# RP_ComputeModule3_rev_3_0.net
KiCad netlist of a schematic drawn in Altium Designer
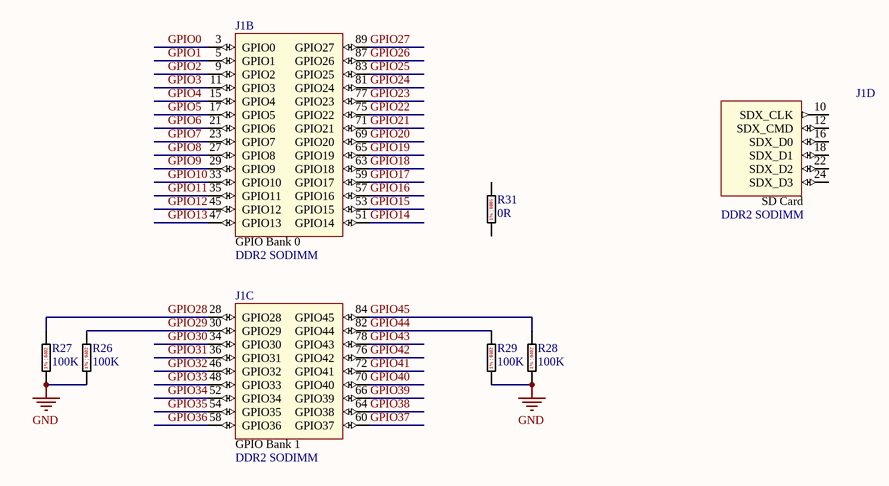
[diagram p0: RP_ComputeModule3_rev.3.0.SchDoc]

(export (version "E")
  (design (tool "Eeschema 10.0.6"))
  (components
    (comp (ref "J1")
      (value "DDR2 SODIMM")
      (footprint "TE 1473005-4 (DDR2 SO-DIMM)")
      (description "TE CONNECTIVITY / AMP         1473005-4             SOCKET IC, DIMM, DDR2, 1.8V, 200WAY")
      (fields
        (field (name "MANUFACTURER") "TE Connectivity")
        (field (name "MANUFACTURER PART NUMBER") "1473005-4")
      )
      (libsource (lib "TEConnectivity_AMP") (part "1473005-4"))
    )
    (comp (ref "R26")
      (value "100K")
      (footprint "RES0402")
      (description "Thick Film Resistors - SMD 0.125W 100Kohm 1% 200ppm")
      (fields
        (field (name "MANUFACTURER") "KOA Speer")
        (field (name "MANUFACTURER PART NUMBER") "SG73P1ETTP1003F")
      )
      (libsource (lib "KOA_Resistors") (part "SG73P1ETTP1003F"))
    )
    (comp (ref "R27")
      (value "100K")
      (footprint "RES0402")
      (description "Thick Film Resistors - SMD 0.125W 100Kohm 1% 200ppm")
      (fields
        (field (name "MANUFACTURER") "KOA Speer")
        (field (name "MANUFACTURER PART NUMBER") "SG73P1ETTP1003F")
      )
      (libsource (lib "KOA_Resistors") (part "SG73P1ETTP1003F"))
    )
    (comp (ref "R28")
      (value "100K")
      (footprint "RES0402")
      (description "Thick Film Resistors - SMD 0.125W 100Kohm 1% 200ppm")
      (fields
        (field (name "MANUFACTURER") "KOA Speer")
        (field (name "MANUFACTURER PART NUMBER") "SG73P1ETTP1003F")
      )
      (libsource (lib "KOA_Resistors") (part "SG73P1ETTP1003F"))
    )
    (comp (ref "R29")
      (value "100K")
      (footprint "RES0402")
      (description "Thick Film Resistors - SMD 0.125W 100Kohm 1% 200ppm")
      (fields
        (field (name "MANUFACTURER") "KOA Speer")
        (field (name "MANUFACTURER PART NUMBER") "SG73P1ETTP1003F")
      )
      (libsource (lib "KOA_Resistors") (part "SG73P1ETTP1003F"))
    )
    (comp (ref "R31")
      (value "0R")
      (footprint "YAGEO RES0402")
      (description "Thick Film Resistors - SMD 1/8W 0.0ohm 1%")
      (fields
        (field (name "MANUFACTURER") "Yageo")
        (field (name "MANUFACTURER PART NUMBER") "AC0805FR-070RL")
      )
      (libsource (lib "YAGEO_Library") (part "AC0805FR-070RL"))
    )
  )
  (nets
    (net (code "1") (name "/GPIO0") (class "Default")
      (node (ref "J1") (pin "3") (pinfunction "GPIO0_3") (pintype "bidirectional"))
    )
    (net (code "2") (name "/GPIO1") (class "Default")
      (node (ref "J1") (pin "5") (pinfunction "GPIO1_5") (pintype "bidirectional"))
    )
    (net (code "3") (name "/GPIO2") (class "Default")
      (node (ref "J1") (pin "9") (pinfunction "GPIO2_9") (pintype "bidirectional"))
    )
    (net (code "4") (name "/GPIO3") (class "Default")
      (node (ref "J1") (pin "11") (pinfunction "GPIO3_11") (pintype "bidirectional"))
    )
    (net (code "5") (name "/GPIO4") (class "Default")
      (node (ref "J1") (pin "15") (pinfunction "GPIO4_15") (pintype "bidirectional"))
    )
    (net (code "6") (name "/GPIO5") (class "Default")
      (node (ref "J1") (pin "17") (pinfunction "GPIO5_17") (pintype "bidirectional"))
    )
    (net (code "7") (name "/GPIO6") (class "Default")
      (node (ref "J1") (pin "21") (pinfunction "GPIO6_21") (pintype "bidirectional"))
    )
    (net (code "8") (name "/GPIO7") (class "Default")
      (node (ref "J1") (pin "23") (pinfunction "GPIO7_23") (pintype "bidirectional"))
    )
    (net (code "9") (name "/GPIO8") (class "Default")
      (node (ref "J1") (pin "27") (pinfunction "GPIO8_27") (pintype "bidirectional"))
    )
    (net (code "10") (name "/GPIO9") (class "Default")
      (node (ref "J1") (pin "29") (pinfunction "GPIO9_29") (pintype "bidirectional"))
    )
    (net (code "11") (name "/GPIO10") (class "Default")
      (node (ref "J1") (pin "33") (pinfunction "GPIO10_33") (pintype "bidirectional"))
    )
    (net (code "12") (name "/GPIO11") (class "Default")
      (node (ref "J1") (pin "35") (pinfunction "GPIO11_35") (pintype "bidirectional"))
    )
    (net (code "13") (name "/GPIO12") (class "Default")
      (node (ref "J1") (pin "45") (pinfunction "GPIO12_45") (pintype "bidirectional"))
    )
    (net (code "14") (name "/GPIO13") (class "Default")
      (node (ref "J1") (pin "47") (pinfunction "GPIO13_47") (pintype "bidirectional"))
    )
    (net (code "15") (name "/GPIO14") (class "Default")
      (node (ref "J1") (pin "51") (pinfunction "GPIO14_51") (pintype "bidirectional"))
    )
    (net (code "16") (name "/GPIO15") (class "Default")
      (node (ref "J1") (pin "53") (pinfunction "GPIO15_53") (pintype "bidirectional"))
    )
    (net (code "17") (name "/GPIO16") (class "Default")
      (node (ref "J1") (pin "57") (pinfunction "GPIO16_57") (pintype "bidirectional"))
    )
    (net (code "18") (name "/GPIO17") (class "Default")
      (node (ref "J1") (pin "59") (pinfunction "GPIO17_59") (pintype "bidirectional"))
    )
    (net (code "19") (name "/GPIO18") (class "Default")
      (node (ref "J1") (pin "63") (pinfunction "GPIO18_63") (pintype "bidirectional"))
    )
    (net (code "20") (name "/GPIO19") (class "Default")
      (node (ref "J1") (pin "65") (pinfunction "GPIO19_65") (pintype "bidirectional"))
    )
    (net (code "21") (name "/GPIO20") (class "Default")
      (node (ref "J1") (pin "69") (pinfunction "GPIO20_69") (pintype "bidirectional"))
    )
    (net (code "22") (name "/GPIO21") (class "Default")
      (node (ref "J1") (pin "71") (pinfunction "GPIO21_71") (pintype "bidirectional"))
    )
    (net (code "23") (name "/GPIO22") (class "Default")
      (node (ref "J1") (pin "75") (pinfunction "GPIO22_75") (pintype "bidirectional"))
    )
    (net (code "24") (name "/GPIO23") (class "Default")
      (node (ref "J1") (pin "77") (pinfunction "GPIO23_77") (pintype "bidirectional"))
    )
    (net (code "25") (name "/GPIO24") (class "Default")
      (node (ref "J1") (pin "81") (pinfunction "GPIO24_81") (pintype "bidirectional"))
    )
    (net (code "26") (name "/GPIO25") (class "Default")
      (node (ref "J1") (pin "83") (pinfunction "GPIO25_83") (pintype "bidirectional"))
    )
    (net (code "27") (name "/GPIO26") (class "Default")
      (node (ref "J1") (pin "87") (pinfunction "GPIO26_87") (pintype "bidirectional"))
    )
    (net (code "28") (name "/GPIO27") (class "Default")
      (node (ref "J1") (pin "89") (pinfunction "GPIO27_89") (pintype "bidirectional"))
    )
    (net (code "29") (name "/GPIO28") (class "Default")
      (node (ref "J1") (pin "28") (pinfunction "GPIO28_28") (pintype "bidirectional"))
      (node (ref "R27") (pin "1") (pinfunction "1_1") (pintype "passive"))
    )
    (net (code "30") (name "/GPIO29") (class "Default")
      (node (ref "J1") (pin "30") (pinfunction "GPIO29_30") (pintype "bidirectional"))
      (node (ref "R26") (pin "1") (pinfunction "1_1") (pintype "passive"))
    )
    (net (code "31") (name "/GPIO30") (class "Default")
      (node (ref "J1") (pin "34") (pinfunction "GPIO30_34") (pintype "bidirectional"))
    )
    (net (code "32") (name "/GPIO31") (class "Default")
      (node (ref "J1") (pin "36") (pinfunction "GPIO31_36") (pintype "bidirectional"))
    )
    (net (code "33") (name "/GPIO32") (class "Default")
      (node (ref "J1") (pin "46") (pinfunction "GPIO32_46") (pintype "bidirectional"))
    )
    (net (code "34") (name "/GPIO33") (class "Default")
      (node (ref "J1") (pin "48") (pinfunction "GPIO33_48") (pintype "bidirectional"))
    )
    (net (code "35") (name "/GPIO34") (class "Default")
      (node (ref "J1") (pin "52") (pinfunction "GPIO34_52") (pintype "bidirectional"))
    )
    (net (code "36") (name "/GPIO35") (class "Default")
      (node (ref "J1") (pin "54") (pinfunction "GPIO35_54") (pintype "bidirectional"))
    )
    (net (code "37") (name "/GPIO36") (class "Default")
      (node (ref "J1") (pin "58") (pinfunction "GPIO36_58") (pintype "bidirectional"))
    )
    (net (code "38") (name "/GPIO37") (class "Default")
      (node (ref "J1") (pin "60") (pinfunction "GPIO37_60") (pintype "bidirectional"))
    )
    (net (code "39") (name "/GPIO38") (class "Default")
      (node (ref "J1") (pin "64") (pinfunction "GPIO38_64") (pintype "bidirectional"))
    )
    (net (code "40") (name "/GPIO39") (class "Default")
      (node (ref "J1") (pin "66") (pinfunction "GPIO39_66") (pintype "bidirectional"))
    )
    (net (code "41") (name "/GPIO40") (class "Default")
      (node (ref "J1") (pin "70") (pinfunction "GPIO40_70") (pintype "bidirectional"))
    )
    (net (code "42") (name "/GPIO41") (class "Default")
      (node (ref "J1") (pin "72") (pinfunction "GPIO41_72") (pintype "bidirectional"))
    )
    (net (code "43") (name "/GPIO42") (class "Default")
      (node (ref "J1") (pin "76") (pinfunction "GPIO42_76") (pintype "bidirectional"))
    )
    (net (code "44") (name "/GPIO43") (class "Default")
      (node (ref "J1") (pin "78") (pinfunction "GPIO43_78") (pintype "bidirectional"))
    )
    (net (code "45") (name "/GPIO44") (class "Default")
      (node (ref "J1") (pin "82") (pinfunction "GPIO44_82") (pintype "bidirectional"))
      (node (ref "R29") (pin "1") (pinfunction "1_1") (pintype "passive"))
    )
    (net (code "46") (name "/GPIO45") (class "Default")
      (node (ref "J1") (pin "84") (pinfunction "GPIO45_84") (pintype "bidirectional"))
      (node (ref "R28") (pin "1") (pinfunction "1_1") (pintype "passive"))
    )
    (net (code "47") (name "GND") (class "Default")
      (node (ref "R26") (pin "2") (pinfunction "2_2") (pintype "passive"))
      (node (ref "R27") (pin "2") (pinfunction "2_2") (pintype "passive"))
      (node (ref "R28") (pin "2") (pinfunction "2_2") (pintype "passive"))
      (node (ref "R29") (pin "2") (pinfunction "2_2") (pintype "passive"))
    )
    (net (code "48") (name "unconnected-(J1D-SDX_CLK-Pad10)") (class "Default")
      (node (ref "J1") (pin "10") (pinfunction "SDX_CLK_10") (pintype "output"))
    )
    (net (code "49") (name "unconnected-(J1D-SDX_CMD-Pad12)") (class "Default")
      (node (ref "J1") (pin "12") (pinfunction "SDX_CMD_12") (pintype "bidirectional"))
    )
    (net (code "50") (name "unconnected-(J1D-SDX_D0-Pad16)") (class "Default")
      (node (ref "J1") (pin "16") (pinfunction "SDX_D0_16") (pintype "bidirectional"))
    )
    (net (code "51") (name "unconnected-(J1D-SDX_D1-Pad18)") (class "Default")
      (node (ref "J1") (pin "18") (pinfunction "SDX_D1_18") (pintype "bidirectional"))
    )
    (net (code "52") (name "unconnected-(J1D-SDX_D2-Pad22)") (class "Default")
      (node (ref "J1") (pin "22") (pinfunction "SDX_D2_22") (pintype "bidirectional"))
    )
    (net (code "53") (name "unconnected-(J1D-SDX_D3-Pad24)") (class "Default")
      (node (ref "J1") (pin "24") (pinfunction "SDX_D3_24") (pintype "bidirectional"))
    )
    (net (code "54") (name "unconnected-(R31-Pad1)") (class "Default")
      (node (ref "R31") (pin "1") (pinfunction "1_1") (pintype "passive"))
    )
    (net (code "55") (name "unconnected-(R31-Pad2)") (class "Default")
      (node (ref "R31") (pin "2") (pinfunction "2_2") (pintype "passive"))
    )
  )
)
